# first.net
KiCad netlist of a schematic drawn in EAGLE
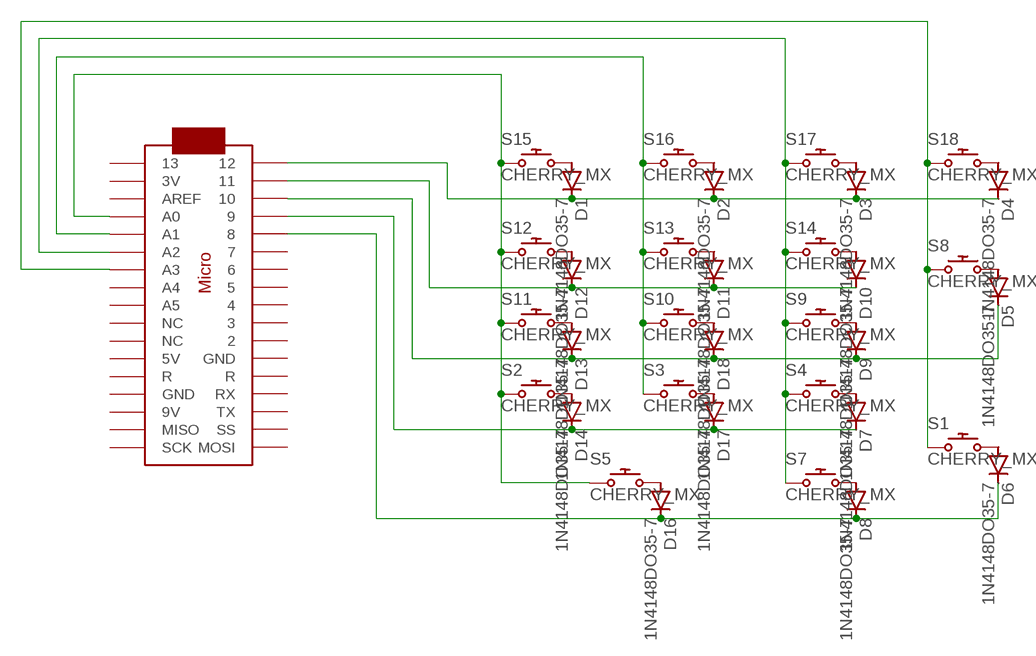
[diagram p0: schematic, sheet 1]

(export (version "E")
  (design (tool "Eeschema 10.0.6"))
  (components
    (comp (ref "D1")
      (value "1N4148DO35-7")
      (footprint "eagle-import:DO35-7")
      (libsource (lib "eagle-import") (part "1N4148DO35-7"))
    )
    (comp (ref "D2")
      (value "1N4148DO35-7")
      (footprint "eagle-import:DO35-7")
      (libsource (lib "eagle-import") (part "1N4148DO35-7"))
    )
    (comp (ref "D3")
      (value "1N4148DO35-7")
      (footprint "eagle-import:DO35-7")
      (libsource (lib "eagle-import") (part "1N4148DO35-7"))
    )
    (comp (ref "D4")
      (value "1N4148DO35-7")
      (footprint "eagle-import:DO35-7")
      (libsource (lib "eagle-import") (part "1N4148DO35-7"))
    )
    (comp (ref "D5")
      (value "1N4148DO35-7")
      (footprint "eagle-import:DO35-7")
      (libsource (lib "eagle-import") (part "1N4148DO35-7"))
    )
    (comp (ref "D6")
      (value "1N4148DO35-7")
      (footprint "eagle-import:DO35-7")
      (libsource (lib "eagle-import") (part "1N4148DO35-7"))
    )
    (comp (ref "D7")
      (value "1N4148DO35-7")
      (footprint "eagle-import:DO35-7")
      (libsource (lib "eagle-import") (part "1N4148DO35-7"))
    )
    (comp (ref "D8")
      (value "1N4148DO35-7")
      (footprint "eagle-import:DO35-7")
      (libsource (lib "eagle-import") (part "1N4148DO35-7"))
    )
    (comp (ref "D9")
      (value "1N4148DO35-7")
      (footprint "eagle-import:DO35-7")
      (libsource (lib "eagle-import") (part "1N4148DO35-7"))
    )
    (comp (ref "D10")
      (value "1N4148DO35-7")
      (footprint "eagle-import:DO35-7")
      (libsource (lib "eagle-import") (part "1N4148DO35-7"))
    )
    (comp (ref "D11")
      (value "1N4148DO35-7")
      (footprint "eagle-import:DO35-7")
      (libsource (lib "eagle-import") (part "1N4148DO35-7"))
    )
    (comp (ref "D12")
      (value "1N4148DO35-7")
      (footprint "eagle-import:DO35-7")
      (libsource (lib "eagle-import") (part "1N4148DO35-7"))
    )
    (comp (ref "D13")
      (value "1N4148DO35-7")
      (footprint "eagle-import:DO35-7")
      (libsource (lib "eagle-import") (part "1N4148DO35-7"))
    )
    (comp (ref "D14")
      (value "1N4148DO35-7")
      (footprint "eagle-import:DO35-7")
      (libsource (lib "eagle-import") (part "1N4148DO35-7"))
    )
    (comp (ref "D16")
      (value "1N4148DO35-7")
      (footprint "eagle-import:DO35-7")
      (libsource (lib "eagle-import") (part "1N4148DO35-7"))
    )
    (comp (ref "D17")
      (value "1N4148DO35-7")
      (footprint "eagle-import:DO35-7")
      (libsource (lib "eagle-import") (part "1N4148DO35-7"))
    )
    (comp (ref "D18")
      (value "1N4148DO35-7")
      (footprint "eagle-import:DO35-7")
      (libsource (lib "eagle-import") (part "1N4148DO35-7"))
    )
    (comp (ref "S1")
      (value "CHERRY_MX")
      (footprint "eagle-import:CHERRY_MX")
      (libsource (lib "eagle-import") (part "CHERRY_MX"))
    )
    (comp (ref "S2")
      (value "CHERRY_MX")
      (footprint "eagle-import:CHERRY_MX")
      (libsource (lib "eagle-import") (part "CHERRY_MX"))
    )
    (comp (ref "S3")
      (value "CHERRY_MX")
      (footprint "eagle-import:CHERRY_MX")
      (libsource (lib "eagle-import") (part "CHERRY_MX"))
    )
    (comp (ref "S4")
      (value "CHERRY_MX")
      (footprint "eagle-import:CHERRY_MX")
      (libsource (lib "eagle-import") (part "CHERRY_MX"))
    )
    (comp (ref "S5")
      (value "CHERRY_MX")
      (footprint "eagle-import:CHERRY_MX")
      (libsource (lib "eagle-import") (part "CHERRY_MX"))
    )
    (comp (ref "S7")
      (value "CHERRY_MX")
      (footprint "eagle-import:CHERRY_MX")
      (libsource (lib "eagle-import") (part "CHERRY_MX"))
    )
    (comp (ref "S8")
      (value "CHERRY_MX")
      (footprint "eagle-import:CHERRY_MX")
      (libsource (lib "eagle-import") (part "CHERRY_MX"))
    )
    (comp (ref "S9")
      (value "CHERRY_MX")
      (footprint "eagle-import:CHERRY_MX")
      (libsource (lib "eagle-import") (part "CHERRY_MX"))
    )
    (comp (ref "S10")
      (value "CHERRY_MX")
      (footprint "eagle-import:CHERRY_MX")
      (libsource (lib "eagle-import") (part "CHERRY_MX"))
    )
    (comp (ref "S11")
      (value "CHERRY_MX")
      (footprint "eagle-import:CHERRY_MX")
      (libsource (lib "eagle-import") (part "CHERRY_MX"))
    )
    (comp (ref "S12")
      (value "CHERRY_MX")
      (footprint "eagle-import:CHERRY_MX")
      (libsource (lib "eagle-import") (part "CHERRY_MX"))
    )
    (comp (ref "S13")
      (value "CHERRY_MX")
      (footprint "eagle-import:CHERRY_MX")
      (libsource (lib "eagle-import") (part "CHERRY_MX"))
    )
    (comp (ref "S14")
      (value "CHERRY_MX")
      (footprint "eagle-import:CHERRY_MX")
      (libsource (lib "eagle-import") (part "CHERRY_MX"))
    )
    (comp (ref "S15")
      (value "CHERRY_MX")
      (footprint "eagle-import:CHERRY_MX")
      (libsource (lib "eagle-import") (part "CHERRY_MX"))
    )
    (comp (ref "S16")
      (value "CHERRY_MX")
      (footprint "eagle-import:CHERRY_MX")
      (libsource (lib "eagle-import") (part "CHERRY_MX"))
    )
    (comp (ref "S17")
      (value "CHERRY_MX")
      (footprint "eagle-import:CHERRY_MX")
      (libsource (lib "eagle-import") (part "CHERRY_MX"))
    )
    (comp (ref "S18")
      (value "CHERRY_MX")
      (footprint "eagle-import:CHERRY_MX")
      (libsource (lib "eagle-import") (part "CHERRY_MX"))
    )
    (comp (ref "U$1")
      (value "ARDUINOMICRO")
      (footprint "eagle-import:ARDUINOMICRO")
      (libsource (lib "eagle-import") (part "ARDUINOMICRO"))
    )
  )
  (nets
    (net (code "1") (name "Net-(S1-1)") (class "Default")
      (node (ref "S1") (pin "S1") (pinfunction "1_S1") (pintype "passive"))
      (node (ref "S18") (pin "S1") (pinfunction "1_S1") (pintype "passive"))
      (node (ref "S8") (pin "S1") (pinfunction "1_S1") (pintype "passive"))
      (node (ref "U$1") (pin "P$28") (pinfunction "A3_P$28") (pintype "bidirectional"))
    )
    (net (code "2") (name "Net-(S1-2)") (class "Default")
      (node (ref "D6") (pin "A") (pinfunction "A_A") (pintype "passive"))
      (node (ref "S1") (pin "S2") (pinfunction "2_S2") (pintype "passive"))
    )
    (net (code "3") (name "Net-(S2-2)") (class "Default")
      (node (ref "D14") (pin "A") (pinfunction "A_A") (pintype "passive"))
      (node (ref "S2") (pin "S2") (pinfunction "2_S2") (pintype "passive"))
    )
    (net (code "4") (name "Net-(S3-2)") (class "Default")
      (node (ref "D17") (pin "A") (pinfunction "A_A") (pintype "passive"))
      (node (ref "S3") (pin "S2") (pinfunction "2_S2") (pintype "passive"))
    )
    (net (code "5") (name "Net-(S4-2)") (class "Default")
      (node (ref "D7") (pin "A") (pinfunction "A_A") (pintype "passive"))
      (node (ref "S4") (pin "S2") (pinfunction "2_S2") (pintype "passive"))
    )
    (net (code "6") (name "Net-(S5-2)") (class "Default")
      (node (ref "D16") (pin "A") (pinfunction "A_A") (pintype "passive"))
      (node (ref "S5") (pin "S2") (pinfunction "2_S2") (pintype "passive"))
    )
    (net (code "7") (name "Net-(S7-2)") (class "Default")
      (node (ref "D8") (pin "A") (pinfunction "A_A") (pintype "passive"))
      (node (ref "S7") (pin "S2") (pinfunction "2_S2") (pintype "passive"))
    )
    (net (code "8") (name "Net-(S8-2)") (class "Default")
      (node (ref "D5") (pin "A") (pinfunction "A_A") (pintype "passive"))
      (node (ref "S8") (pin "S2") (pinfunction "2_S2") (pintype "passive"))
    )
    (net (code "9") (name "Net-(S9-2)") (class "Default")
      (node (ref "D9") (pin "A") (pinfunction "A_A") (pintype "passive"))
      (node (ref "S9") (pin "S2") (pinfunction "2_S2") (pintype "passive"))
    )
    (net (code "10") (name "Net-(S10-1)") (class "Default")
      (node (ref "S10") (pin "S1") (pinfunction "1_S1") (pintype "passive"))
      (node (ref "S13") (pin "S1") (pinfunction "1_S1") (pintype "passive"))
      (node (ref "S16") (pin "S1") (pinfunction "1_S1") (pintype "passive"))
      (node (ref "S3") (pin "S1") (pinfunction "1_S1") (pintype "passive"))
      (node (ref "U$1") (pin "P$30") (pinfunction "A1_P$30") (pintype "bidirectional"))
    )
    (net (code "11") (name "Net-(S10-2)") (class "Default")
      (node (ref "D18") (pin "A") (pinfunction "A_A") (pintype "passive"))
      (node (ref "S10") (pin "S2") (pinfunction "2_S2") (pintype "passive"))
    )
    (net (code "12") (name "Net-(S11-1)") (class "Default")
      (node (ref "S11") (pin "S1") (pinfunction "1_S1") (pintype "passive"))
      (node (ref "S12") (pin "S1") (pinfunction "1_S1") (pintype "passive"))
      (node (ref "S15") (pin "S1") (pinfunction "1_S1") (pintype "passive"))
      (node (ref "S2") (pin "S1") (pinfunction "1_S1") (pintype "passive"))
      (node (ref "S5") (pin "S1") (pinfunction "1_S1") (pintype "passive"))
      (node (ref "U$1") (pin "P$31") (pinfunction "A0_P$31") (pintype "bidirectional"))
    )
    (net (code "13") (name "Net-(S11-2)") (class "Default")
      (node (ref "D13") (pin "A") (pinfunction "A_A") (pintype "passive"))
      (node (ref "S11") (pin "S2") (pinfunction "2_S2") (pintype "passive"))
    )
    (net (code "14") (name "Net-(S12-2)") (class "Default")
      (node (ref "D12") (pin "A") (pinfunction "A_A") (pintype "passive"))
      (node (ref "S12") (pin "S2") (pinfunction "2_S2") (pintype "passive"))
    )
    (net (code "15") (name "Net-(S13-2)") (class "Default")
      (node (ref "D11") (pin "A") (pinfunction "A_A") (pintype "passive"))
      (node (ref "S13") (pin "S2") (pinfunction "2_S2") (pintype "passive"))
    )
    (net (code "16") (name "Net-(S14-1)") (class "Default")
      (node (ref "S14") (pin "S1") (pinfunction "1_S1") (pintype "passive"))
      (node (ref "S17") (pin "S1") (pinfunction "1_S1") (pintype "passive"))
      (node (ref "S4") (pin "S1") (pinfunction "1_S1") (pintype "passive"))
      (node (ref "S7") (pin "S1") (pinfunction "1_S1") (pintype "passive"))
      (node (ref "S9") (pin "S1") (pinfunction "1_S1") (pintype "passive"))
      (node (ref "U$1") (pin "P$29") (pinfunction "A2_P$29") (pintype "bidirectional"))
    )
    (net (code "17") (name "Net-(S14-2)") (class "Default")
      (node (ref "D10") (pin "A") (pinfunction "A_A") (pintype "passive"))
      (node (ref "S14") (pin "S2") (pinfunction "2_S2") (pintype "passive"))
    )
    (net (code "18") (name "Net-(S15-2)") (class "Default")
      (node (ref "D1") (pin "A") (pinfunction "A_A") (pintype "passive"))
      (node (ref "S15") (pin "S2") (pinfunction "2_S2") (pintype "passive"))
    )
    (net (code "19") (name "Net-(S16-2)") (class "Default")
      (node (ref "D2") (pin "A") (pinfunction "A_A") (pintype "passive"))
      (node (ref "S16") (pin "S2") (pinfunction "2_S2") (pintype "passive"))
    )
    (net (code "20") (name "Net-(S17-2)") (class "Default")
      (node (ref "D3") (pin "A") (pinfunction "A_A") (pintype "passive"))
      (node (ref "S17") (pin "S2") (pinfunction "2_S2") (pintype "passive"))
    )
    (net (code "21") (name "Net-(S18-2)") (class "Default")
      (node (ref "D4") (pin "A") (pinfunction "A_A") (pintype "passive"))
      (node (ref "S18") (pin "S2") (pinfunction "2_S2") (pintype "passive"))
    )
    (net (code "22") (name "Net-(U$1-8)") (class "Default")
      (node (ref "D16") (pin "C") (pinfunction "C_C") (pintype "passive"))
      (node (ref "D6") (pin "C") (pinfunction "C_C") (pintype "passive"))
      (node (ref "D8") (pin "C") (pinfunction "C_C") (pintype "passive"))
      (node (ref "U$1") (pin "P$5") (pinfunction "8_P$5") (pintype "bidirectional"))
    )
    (net (code "23") (name "Net-(U$1-9)") (class "Default")
      (node (ref "D14") (pin "C") (pinfunction "C_C") (pintype "passive"))
      (node (ref "D17") (pin "C") (pinfunction "C_C") (pintype "passive"))
      (node (ref "D7") (pin "C") (pinfunction "C_C") (pintype "passive"))
      (node (ref "U$1") (pin "P$4") (pinfunction "9_P$4") (pintype "bidirectional"))
    )
    (net (code "24") (name "Net-(U$1-10)") (class "Default")
      (node (ref "D13") (pin "C") (pinfunction "C_C") (pintype "passive"))
      (node (ref "D18") (pin "C") (pinfunction "C_C") (pintype "passive"))
      (node (ref "D5") (pin "C") (pinfunction "C_C") (pintype "passive"))
      (node (ref "D9") (pin "C") (pinfunction "C_C") (pintype "passive"))
      (node (ref "U$1") (pin "P$3") (pinfunction "10_P$3") (pintype "bidirectional"))
    )
    (net (code "25") (name "Net-(U$1-11)") (class "Default")
      (node (ref "D10") (pin "C") (pinfunction "C_C") (pintype "passive"))
      (node (ref "D11") (pin "C") (pinfunction "C_C") (pintype "passive"))
      (node (ref "D12") (pin "C") (pinfunction "C_C") (pintype "passive"))
      (node (ref "U$1") (pin "P$2") (pinfunction "11_P$2") (pintype "bidirectional"))
    )
    (net (code "26") (name "Net-(U$1-12)") (class "Default")
      (node (ref "D1") (pin "C") (pinfunction "C_C") (pintype "passive"))
      (node (ref "D2") (pin "C") (pinfunction "C_C") (pintype "passive"))
      (node (ref "D3") (pin "C") (pinfunction "C_C") (pintype "passive"))
      (node (ref "D4") (pin "C") (pinfunction "C_C") (pintype "passive"))
      (node (ref "U$1") (pin "P$1") (pinfunction "12_P$1") (pintype "bidirectional"))
    )
    (net (code "27") (name "unconnected-(U$1-2-PadP$11)") (class "Default")
      (node (ref "U$1") (pin "P$11") (pinfunction "2_P$11") (pintype "bidirectional"))
    )
    (net (code "28") (name "unconnected-(U$1-3-PadP$10)") (class "Default")
      (node (ref "U$1") (pin "P$10") (pinfunction "3_P$10") (pintype "bidirectional"))
    )
    (net (code "29") (name "unconnected-(U$1-3V-PadP$33)") (class "Default")
      (node (ref "U$1") (pin "P$33") (pinfunction "3V_P$33") (pintype "bidirectional"))
    )
    (net (code "30") (name "unconnected-(U$1-4-PadP$9)") (class "Default")
      (node (ref "U$1") (pin "P$9") (pinfunction "4_P$9") (pintype "bidirectional"))
    )
    (net (code "31") (name "unconnected-(U$1-5-PadP$8)") (class "Default")
      (node (ref "U$1") (pin "P$8") (pinfunction "5_P$8") (pintype "bidirectional"))
    )
    (net (code "32") (name "unconnected-(U$1-5V-PadP$23)") (class "Default")
      (node (ref "U$1") (pin "P$23") (pinfunction "5V_P$23") (pintype "bidirectional"))
    )
    (net (code "33") (name "unconnected-(U$1-6-PadP$7)") (class "Default")
      (node (ref "U$1") (pin "P$7") (pinfunction "6_P$7") (pintype "bidirectional"))
    )
    (net (code "34") (name "unconnected-(U$1-7-PadP$6)") (class "Default")
      (node (ref "U$1") (pin "P$6") (pinfunction "7_P$6") (pintype "bidirectional"))
    )
    (net (code "35") (name "unconnected-(U$1-9V-PadP$20)") (class "Default")
      (node (ref "U$1") (pin "P$20") (pinfunction "9V_P$20") (pintype "bidirectional"))
    )
    (net (code "36") (name "unconnected-(U$1-13-PadP$34)") (class "Default")
      (node (ref "U$1") (pin "P$34") (pinfunction "13_P$34") (pintype "bidirectional"))
    )
    (net (code "37") (name "unconnected-(U$1-A4-PadP$27)") (class "Default")
      (node (ref "U$1") (pin "P$27") (pinfunction "A4_P$27") (pintype "bidirectional"))
    )
    (net (code "38") (name "unconnected-(U$1-A5-PadP$26)") (class "Default")
      (node (ref "U$1") (pin "P$26") (pinfunction "A5_P$26") (pintype "bidirectional"))
    )
    (net (code "39") (name "unconnected-(U$1-AREF-PadP$32)") (class "Default")
      (node (ref "U$1") (pin "P$32") (pinfunction "AREF_P$32") (pintype "bidirectional"))
    )
    (net (code "40") (name "unconnected-(U$1-GND-PadP$12)") (class "Default")
      (node (ref "U$1") (pin "P$12") (pinfunction "GND_P$12") (pintype "bidirectional"))
    )
    (net (code "41") (name "unconnected-(U$1-GND-PadP$21)") (class "Default")
      (node (ref "U$1") (pin "P$21") (pinfunction "GND_P$21") (pintype "bidirectional"))
    )
    (net (code "42") (name "unconnected-(U$1-MISO-PadP$19)") (class "Default")
      (node (ref "U$1") (pin "P$19") (pinfunction "MISO_P$19") (pintype "bidirectional"))
    )
    (net (code "43") (name "unconnected-(U$1-MOSI-PadP$17)") (class "Default")
      (node (ref "U$1") (pin "P$17") (pinfunction "MOSI_P$17") (pintype "bidirectional"))
    )
    (net (code "44") (name "unconnected-(U$1-NC-PadP$24)") (class "Default")
      (node (ref "U$1") (pin "P$24") (pinfunction "NC_P$24") (pintype "bidirectional"))
    )
    (net (code "45") (name "unconnected-(U$1-NC-PadP$25)") (class "Default")
      (node (ref "U$1") (pin "P$25") (pinfunction "NC_P$25") (pintype "bidirectional"))
    )
    (net (code "46") (name "unconnected-(U$1-R-PadP$13)") (class "Default")
      (node (ref "U$1") (pin "P$13") (pinfunction "R_P$13") (pintype "bidirectional"))
    )
    (net (code "47") (name "unconnected-(U$1-R-PadP$22)") (class "Default")
      (node (ref "U$1") (pin "P$22") (pinfunction "R_P$22") (pintype "bidirectional"))
    )
    (net (code "48") (name "unconnected-(U$1-RX-PadP$14)") (class "Default")
      (node (ref "U$1") (pin "P$14") (pinfunction "RX_P$14") (pintype "bidirectional"))
    )
    (net (code "49") (name "unconnected-(U$1-SCK-PadP$18)") (class "Default")
      (node (ref "U$1") (pin "P$18") (pinfunction "SCK_P$18") (pintype "bidirectional"))
    )
    (net (code "50") (name "unconnected-(U$1-SS-PadP$16)") (class "Default")
      (node (ref "U$1") (pin "P$16") (pinfunction "SS_P$16") (pintype "bidirectional"))
    )
    (net (code "51") (name "unconnected-(U$1-TX-PadP$15)") (class "Default")
      (node (ref "U$1") (pin "P$15") (pinfunction "TX_P$15") (pintype "bidirectional"))
    )
  )
)
